# Keg_Cop_-_Daisy_Chain_T_with_Slots.net
KiCad netlist of a schematic drawn in EAGLE
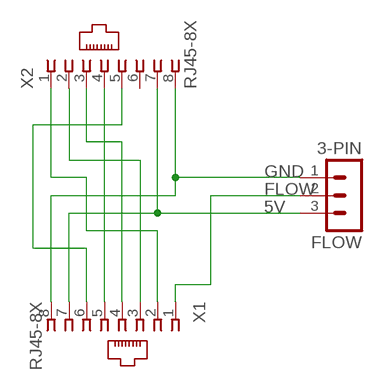
[diagram p0: schematic, sheet 1]

(export (version "E")
  (design (tool "Eeschema 10.0.6"))
  (components
    (comp (ref "FLOW")
      (value "3-PIN")
      (footprint "eagle-import:HDR-3_VERT")
      (libsource (lib "eagle-import") (part "HDR-3"))
    )
    (comp (ref "X1")
      (value "RJ45-8X")
      (footprint "eagle-import:RJ45-NO-SHIELD")
      (libsource (lib "eagle-import") (part "RJ45-8X"))
    )
    (comp (ref "X2")
      (value "RJ45-8X")
      (footprint "eagle-import:RJ45-NO-SHIELD")
      (libsource (lib "eagle-import") (part "RJ45-8X"))
    )
  )
  (nets
    (net (code "1") (name "/5V") (class "Default")
      (node (ref "FLOW") (pin "3") (pinfunction "3_3") (pintype "passive"))
      (node (ref "X1") (pin "7") (pinfunction "7_7") (pintype "passive"))
      (node (ref "X2") (pin "7") (pinfunction "7_7") (pintype "passive"))
    )
    (net (code "2") (name "/FLOW") (class "Default")
      (node (ref "FLOW") (pin "2") (pinfunction "2_2") (pintype "passive"))
      (node (ref "X1") (pin "1") (pinfunction "1_1") (pintype "passive"))
    )
    (net (code "3") (name "/GND") (class "Default")
      (node (ref "FLOW") (pin "1") (pinfunction "1_1") (pintype "passive"))
      (node (ref "X1") (pin "8") (pinfunction "8_8") (pintype "passive"))
      (node (ref "X2") (pin "8") (pinfunction "8_8") (pintype "passive"))
    )
    (net (code "4") (name "Net-(X1-Pad2)") (class "Default")
      (node (ref "X1") (pin "2") (pinfunction "2_2") (pintype "passive"))
      (node (ref "X2") (pin "1") (pinfunction "1_1") (pintype "passive"))
    )
    (net (code "5") (name "Net-(X1-Pad3)") (class "Default")
      (node (ref "X1") (pin "3") (pinfunction "3_3") (pintype "passive"))
      (node (ref "X2") (pin "2") (pinfunction "2_2") (pintype "passive"))
    )
    (net (code "6") (name "Net-(X1-Pad4)") (class "Default")
      (node (ref "X1") (pin "4") (pinfunction "4_4") (pintype "passive"))
      (node (ref "X2") (pin "3") (pinfunction "3_3") (pintype "passive"))
    )
    (net (code "7") (name "Net-(X1-Pad5)") (class "Default")
      (node (ref "X1") (pin "5") (pinfunction "5_5") (pintype "passive"))
      (node (ref "X2") (pin "4") (pinfunction "4_4") (pintype "passive"))
    )
    (net (code "8") (name "Net-(X1-Pad6)") (class "Default")
      (node (ref "X1") (pin "6") (pinfunction "6_6") (pintype "passive"))
      (node (ref "X2") (pin "5") (pinfunction "5_5") (pintype "passive"))
    )
    (net (code "9") (name "unconnected-(X2-Pad6)") (class "Default")
      (node (ref "X2") (pin "6") (pinfunction "6_6") (pintype "passive"))
    )
  )
)
